# boardv02.net
KiCad netlist of a schematic drawn in EAGLE
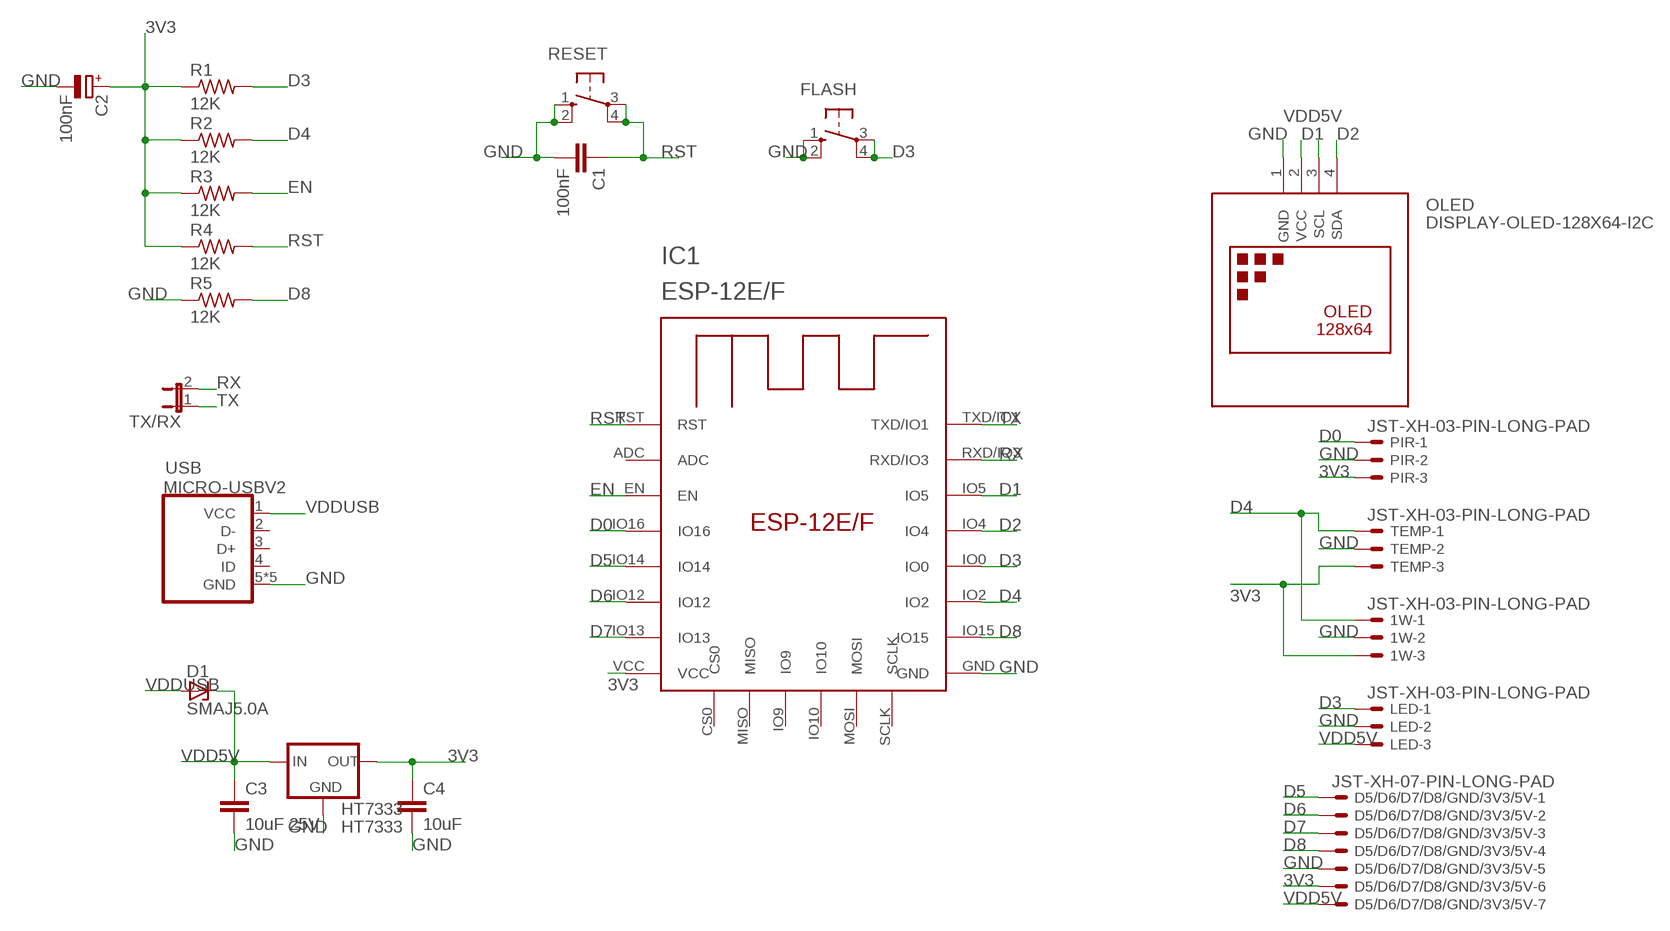
[diagram p0: schematic, sheet 1]

(export (version "E")
  (design (tool "Eeschema 10.0.6"))
  (components
    (comp (ref "1W")
      (value "JST-XH-03-PIN-LONG-PAD")
      (footprint "eagle-import:JST-XH-03-PACKAGE-LONG-PAD")
      (libsource (lib "eagle-import") (part "JST-XH-03-PIN-LONG-PAD"))
    )
    (comp (ref "C1")
      (value "100nF")
      (footprint "eagle-import:C0805")
      (libsource (lib "eagle-import") (part "C-EUC0805"))
    )
    (comp (ref "C2")
      (value "100nF")
      (footprint "eagle-import:R_2012-12R")
      (libsource (lib "eagle-import") (part "CPOL-EUR/2012-12R"))
    )
    (comp (ref "C3")
      (value "10uF 25V")
      (footprint "eagle-import:C0805")
      (libsource (lib "eagle-import") (part "C-EUC0805"))
    )
    (comp (ref "C4")
      (value "10uF")
      (footprint "eagle-import:C0805")
      (libsource (lib "eagle-import") (part "C-EUC0805"))
    )
    (comp (ref "D1")
      (value "SMAJ5.0A")
      (footprint "eagle-import:DO214AC")
      (fields (field (name "MF") "Littelfuse"))
      (libsource (lib "eagle-import") (part "SMAJA5.0"))
    )
    (comp (ref "D5/D6/D7/D8/GND/3V3/5V")
      (value "JST-XH-07-PIN-LONG-PAD")
      (footprint "eagle-import:JST-XH-07-PACKAGE-LONG-PAD")
      (libsource (lib "eagle-import") (part "JST-XH-07-PIN-LONG-PAD"))
    )
    (comp (ref "FLASH")
      (value "10-XX")
      (footprint "eagle-import:B3F-10XX")
      (fields (field (name "MPN") "B3F-1000"))
      (libsource (lib "eagle-import") (part "10-XX"))
    )
    (comp (ref "HT7333")
      (value "HT7333")
      (footprint "eagle-import:SOT-89")
      (libsource (lib "eagle-import") (part "HT7333"))
    )
    (comp (ref "IC1")
      (value "ESP-12E/F")
      (footprint "eagle-import:ESP-12E")
      (libsource (lib "eagle-import") (part "ESP-12E/F"))
    )
    (comp (ref "LED")
      (value "JST-XH-03-PIN-LONG-PAD")
      (footprint "eagle-import:JST-XH-03-PACKAGE-LONG-PAD")
      (libsource (lib "eagle-import") (part "JST-XH-03-PIN-LONG-PAD"))
    )
    (comp (ref "OLED")
      (value "DISPLAY-OLED-128X64-I2C")
      (footprint "eagle-import:DISPLAY-OLED-128X64-I2C")
      (libsource (lib "eagle-import") (part "DISPLAY-OLED-128X64-I2C"))
    )
    (comp (ref "PIR")
      (value "JST-XH-03-PIN-LONG-PAD")
      (footprint "eagle-import:JST-XH-03-PACKAGE-LONG-PAD")
      (libsource (lib "eagle-import") (part "JST-XH-03-PIN-LONG-PAD"))
    )
    (comp (ref "R1")
      (value "12K")
      (footprint "eagle-import:R1206")
      (fields (field (name "SPICEPREFIX") "R"))
      (libsource (lib "eagle-import") (part "R-US_R1206"))
    )
    (comp (ref "R2")
      (value "12K")
      (footprint "eagle-import:R1206")
      (libsource (lib "eagle-import") (part "R-US_R1206"))
    )
    (comp (ref "R3")
      (value "12K")
      (footprint "eagle-import:R1206")
      (libsource (lib "eagle-import") (part "R-US_R1206"))
    )
    (comp (ref "R4")
      (value "12K")
      (footprint "eagle-import:R1206")
      (libsource (lib "eagle-import") (part "R-US_R1206"))
    )
    (comp (ref "R5")
      (value "12K")
      (footprint "eagle-import:R1206")
      (libsource (lib "eagle-import") (part "R-US_R1206"))
    )
    (comp (ref "RESET")
      (value "10-XX")
      (footprint "eagle-import:B3F-10XX")
      (fields (field (name "MPN") "B3F-1000"))
      (libsource (lib "eagle-import") (part "10-XX"))
    )
    (comp (ref "TEMP")
      (value "JST-XH-03-PIN-LONG-PAD")
      (footprint "eagle-import:JST-XH-03-PACKAGE-LONG-PAD")
      (libsource (lib "eagle-import") (part "JST-XH-03-PIN-LONG-PAD"))
    )
    (comp (ref "TX/RX")
      (value "JP1E")
      (footprint "eagle-import:JP1")
      (libsource (lib "eagle-import") (part "JP1E"))
    )
    (comp (ref "USB")
      (value "MICRO-USBV2")
      (footprint "eagle-import:MICRO-USB-2")
      (libsource (lib "eagle-import") (part "MICRO-USBV2"))
    )
  )
  (nets
    (net (code "1") (name "/3V3") (class "Default")
      (node (ref "1W") (pin "3") (pinfunction "S_3") (pintype "passive"))
      (node (ref "C2") (pin "+") (pinfunction "+_+") (pintype "passive"))
      (node (ref "C4") (pin "1") (pinfunction "1_1") (pintype "passive"))
      (node (ref "D5/D6/D7/D8/GND/3V3/5V") (pin "6") (pinfunction "S_6") (pintype "passive"))
      (node (ref "HT7333") (pin "1") (pinfunction "OUT_1") (pintype "passive"))
      (node (ref "IC1") (pin "VCC") (pinfunction "VCC_VCC") (pintype "power_in"))
      (node (ref "PIR") (pin "3") (pinfunction "S_3") (pintype "passive"))
      (node (ref "R1") (pin "1") (pinfunction "1_1") (pintype "passive"))
      (node (ref "R2") (pin "1") (pinfunction "1_1") (pintype "passive"))
      (node (ref "R3") (pin "1") (pinfunction "1_1") (pintype "passive"))
      (node (ref "R4") (pin "1") (pinfunction "1_1") (pintype "passive"))
      (node (ref "TEMP") (pin "3") (pinfunction "S_3") (pintype "passive"))
    )
    (net (code "2") (name "/D0") (class "Default")
      (node (ref "IC1") (pin "IO16") (pinfunction "IO16_IO16") (pintype "bidirectional"))
      (node (ref "PIR") (pin "1") (pinfunction "S_1") (pintype "passive"))
    )
    (net (code "3") (name "/D1") (class "Default")
      (node (ref "IC1") (pin "IO5") (pinfunction "IO5_IO5") (pintype "bidirectional"))
      (node (ref "OLED") (pin "3") (pinfunction "SCL_3") (pintype "bidirectional"))
    )
    (net (code "4") (name "/D2") (class "Default")
      (node (ref "IC1") (pin "IO4") (pinfunction "IO4_IO4") (pintype "bidirectional"))
      (node (ref "OLED") (pin "4") (pinfunction "SDA_4") (pintype "bidirectional"))
    )
    (net (code "5") (name "/D3") (class "Default")
      (node (ref "FLASH") (pin "3") (pinfunction "P_3") (pintype "passive"))
      (node (ref "FLASH") (pin "4") (pinfunction "P1_4") (pintype "passive"))
      (node (ref "IC1") (pin "IO0") (pinfunction "IO0_IO0") (pintype "bidirectional"))
      (node (ref "LED") (pin "1") (pinfunction "S_1") (pintype "passive"))
      (node (ref "R1") (pin "2") (pinfunction "2_2") (pintype "passive"))
    )
    (net (code "6") (name "/D4") (class "Default")
      (node (ref "1W") (pin "1") (pinfunction "S_1") (pintype "passive"))
      (node (ref "IC1") (pin "IO2") (pinfunction "IO2_IO2") (pintype "bidirectional"))
      (node (ref "R2") (pin "2") (pinfunction "2_2") (pintype "passive"))
      (node (ref "TEMP") (pin "1") (pinfunction "S_1") (pintype "passive"))
    )
    (net (code "7") (name "/D5") (class "Default")
      (node (ref "D5/D6/D7/D8/GND/3V3/5V") (pin "1") (pinfunction "S_1") (pintype "passive"))
      (node (ref "IC1") (pin "IO14") (pinfunction "IO14_IO14") (pintype "bidirectional"))
    )
    (net (code "8") (name "/D6") (class "Default")
      (node (ref "D5/D6/D7/D8/GND/3V3/5V") (pin "2") (pinfunction "S_2") (pintype "passive"))
      (node (ref "IC1") (pin "IO12") (pinfunction "IO12_IO12") (pintype "bidirectional"))
    )
    (net (code "9") (name "/D7") (class "Default")
      (node (ref "D5/D6/D7/D8/GND/3V3/5V") (pin "3") (pinfunction "S_3") (pintype "passive"))
      (node (ref "IC1") (pin "IO13") (pinfunction "IO13_IO13") (pintype "bidirectional"))
    )
    (net (code "10") (name "/D8") (class "Default")
      (node (ref "D5/D6/D7/D8/GND/3V3/5V") (pin "4") (pinfunction "S_4") (pintype "passive"))
      (node (ref "IC1") (pin "IO15") (pinfunction "IO15_IO15") (pintype "bidirectional"))
      (node (ref "R5") (pin "2") (pinfunction "2_2") (pintype "passive"))
    )
    (net (code "11") (name "/EN") (class "Default")
      (node (ref "IC1") (pin "EN") (pinfunction "EN_EN") (pintype "bidirectional"))
      (node (ref "R3") (pin "2") (pinfunction "2_2") (pintype "passive"))
    )
    (net (code "12") (name "/GND") (class "Default")
      (node (ref "1W") (pin "2") (pinfunction "S_2") (pintype "passive"))
      (node (ref "C1") (pin "2") (pinfunction "2_2") (pintype "passive"))
      (node (ref "C2") (pin "-") (pinfunction "-_-") (pintype "passive"))
      (node (ref "C3") (pin "2") (pinfunction "2_2") (pintype "passive"))
      (node (ref "C4") (pin "2") (pinfunction "2_2") (pintype "passive"))
      (node (ref "D5/D6/D7/D8/GND/3V3/5V") (pin "5") (pinfunction "S_5") (pintype "passive"))
      (node (ref "FLASH") (pin "1") (pinfunction "S_1") (pintype "passive"))
      (node (ref "FLASH") (pin "2") (pinfunction "S1_2") (pintype "passive"))
      (node (ref "HT7333") (pin "2") (pinfunction "GND_2") (pintype "input"))
      (node (ref "IC1") (pin "GND") (pinfunction "GND_GND") (pintype "power_in"))
      (node (ref "LED") (pin "2") (pinfunction "S_2") (pintype "passive"))
      (node (ref "OLED") (pin "1") (pinfunction "GND_1") (pintype "power_in"))
      (node (ref "PIR") (pin "2") (pinfunction "S_2") (pintype "passive"))
      (node (ref "R5") (pin "1") (pinfunction "1_1") (pintype "passive"))
      (node (ref "RESET") (pin "1") (pinfunction "S_1") (pintype "passive"))
      (node (ref "RESET") (pin "2") (pinfunction "S1_2") (pintype "passive"))
      (node (ref "TEMP") (pin "2") (pinfunction "S_2") (pintype "passive"))
      (node (ref "USB") (pin "5") (pinfunction "GND_5") (pintype "power_in"))
      (node (ref "USB") (pin "P$1") (pinfunction "GND_P$1") (pintype "power_in"))
      (node (ref "USB") (pin "P$2") (pinfunction "GND_P$2") (pintype "power_in"))
      (node (ref "USB") (pin "P$3") (pinfunction "GND_P$3") (pintype "power_in"))
      (node (ref "USB") (pin "P$4") (pinfunction "GND_P$4") (pintype "power_in"))
    )
    (net (code "13") (name "/RST") (class "Default")
      (node (ref "C1") (pin "1") (pinfunction "1_1") (pintype "passive"))
      (node (ref "IC1") (pin "RST") (pinfunction "RST_RST") (pintype "input"))
      (node (ref "R4") (pin "2") (pinfunction "2_2") (pintype "passive"))
      (node (ref "RESET") (pin "3") (pinfunction "P_3") (pintype "passive"))
      (node (ref "RESET") (pin "4") (pinfunction "P1_4") (pintype "passive"))
    )
    (net (code "14") (name "/RX") (class "Default")
      (node (ref "IC1") (pin "RXD/IO3") (pinfunction "RXD/IO3_RXD/IO3") (pintype "bidirectional"))
      (node (ref "TX/RX") (pin "2") (pinfunction "2_2") (pintype "passive"))
    )
    (net (code "15") (name "/TX") (class "Default")
      (node (ref "IC1") (pin "TXD/IO1") (pinfunction "TXD/IO1_TXD/IO1") (pintype "bidirectional"))
      (node (ref "TX/RX") (pin "1") (pinfunction "1_1") (pintype "passive"))
    )
    (net (code "16") (name "/VDD5V") (class "Default")
      (node (ref "C3") (pin "1") (pinfunction "1_1") (pintype "passive"))
      (node (ref "D1") (pin "C") (pinfunction "C_C") (pintype "passive"))
      (node (ref "D5/D6/D7/D8/GND/3V3/5V") (pin "7") (pinfunction "S_7") (pintype "passive"))
      (node (ref "HT7333") (pin "3") (pinfunction "IN_3") (pintype "input"))
      (node (ref "HT7333") (pin "4") (pinfunction "IN_4") (pintype "input"))
      (node (ref "LED") (pin "3") (pinfunction "S_3") (pintype "passive"))
      (node (ref "OLED") (pin "2") (pinfunction "VCC_2") (pintype "power_in"))
    )
    (net (code "17") (name "/VDDUSB") (class "Default")
      (node (ref "D1") (pin "A") (pinfunction "A_A") (pintype "passive"))
      (node (ref "USB") (pin "1") (pinfunction "VCC_1") (pintype "power_in"))
    )
    (net (code "18") (name "unconnected-(IC1-PadADC)") (class "Default")
      (node (ref "IC1") (pin "ADC") (pinfunction "ADC_ADC") (pintype "bidirectional"))
    )
    (net (code "19") (name "unconnected-(IC1-PadCS0)") (class "Default")
      (node (ref "IC1") (pin "CS0") (pinfunction "CS0_CS0") (pintype "bidirectional"))
    )
    (net (code "20") (name "unconnected-(IC1-PadIO9)") (class "Default")
      (node (ref "IC1") (pin "IO9") (pinfunction "IO9_IO9") (pintype "bidirectional"))
    )
    (net (code "21") (name "unconnected-(IC1-PadIO10)") (class "Default")
      (node (ref "IC1") (pin "IO10") (pinfunction "IO10_IO10") (pintype "bidirectional"))
    )
    (net (code "22") (name "unconnected-(IC1-PadMISO)") (class "Default")
      (node (ref "IC1") (pin "MISO") (pinfunction "MISO_MISO") (pintype "bidirectional"))
    )
    (net (code "23") (name "unconnected-(IC1-PadMOSI)") (class "Default")
      (node (ref "IC1") (pin "MOSI") (pinfunction "MOSI_MOSI") (pintype "bidirectional"))
    )
    (net (code "24") (name "unconnected-(IC1-PadSCLK)") (class "Default")
      (node (ref "IC1") (pin "SCLK") (pinfunction "SCLK_SCLK") (pintype "bidirectional"))
    )
    (net (code "25") (name "unconnected-(USB-D+-Pad3)") (class "Default")
      (node (ref "USB") (pin "3") (pinfunction "D+_3") (pintype "bidirectional"))
    )
    (net (code "26") (name "unconnected-(USB-D--Pad2)") (class "Default")
      (node (ref "USB") (pin "2") (pinfunction "D-_2") (pintype "bidirectional"))
    )
    (net (code "27") (name "unconnected-(USB-ID-Pad4)") (class "Default")
      (node (ref "USB") (pin "4") (pinfunction "ID_4") (pintype "bidirectional"))
    )
  )
)
